# wireless.net
KiCad netlist of a schematic drawn in EAGLE
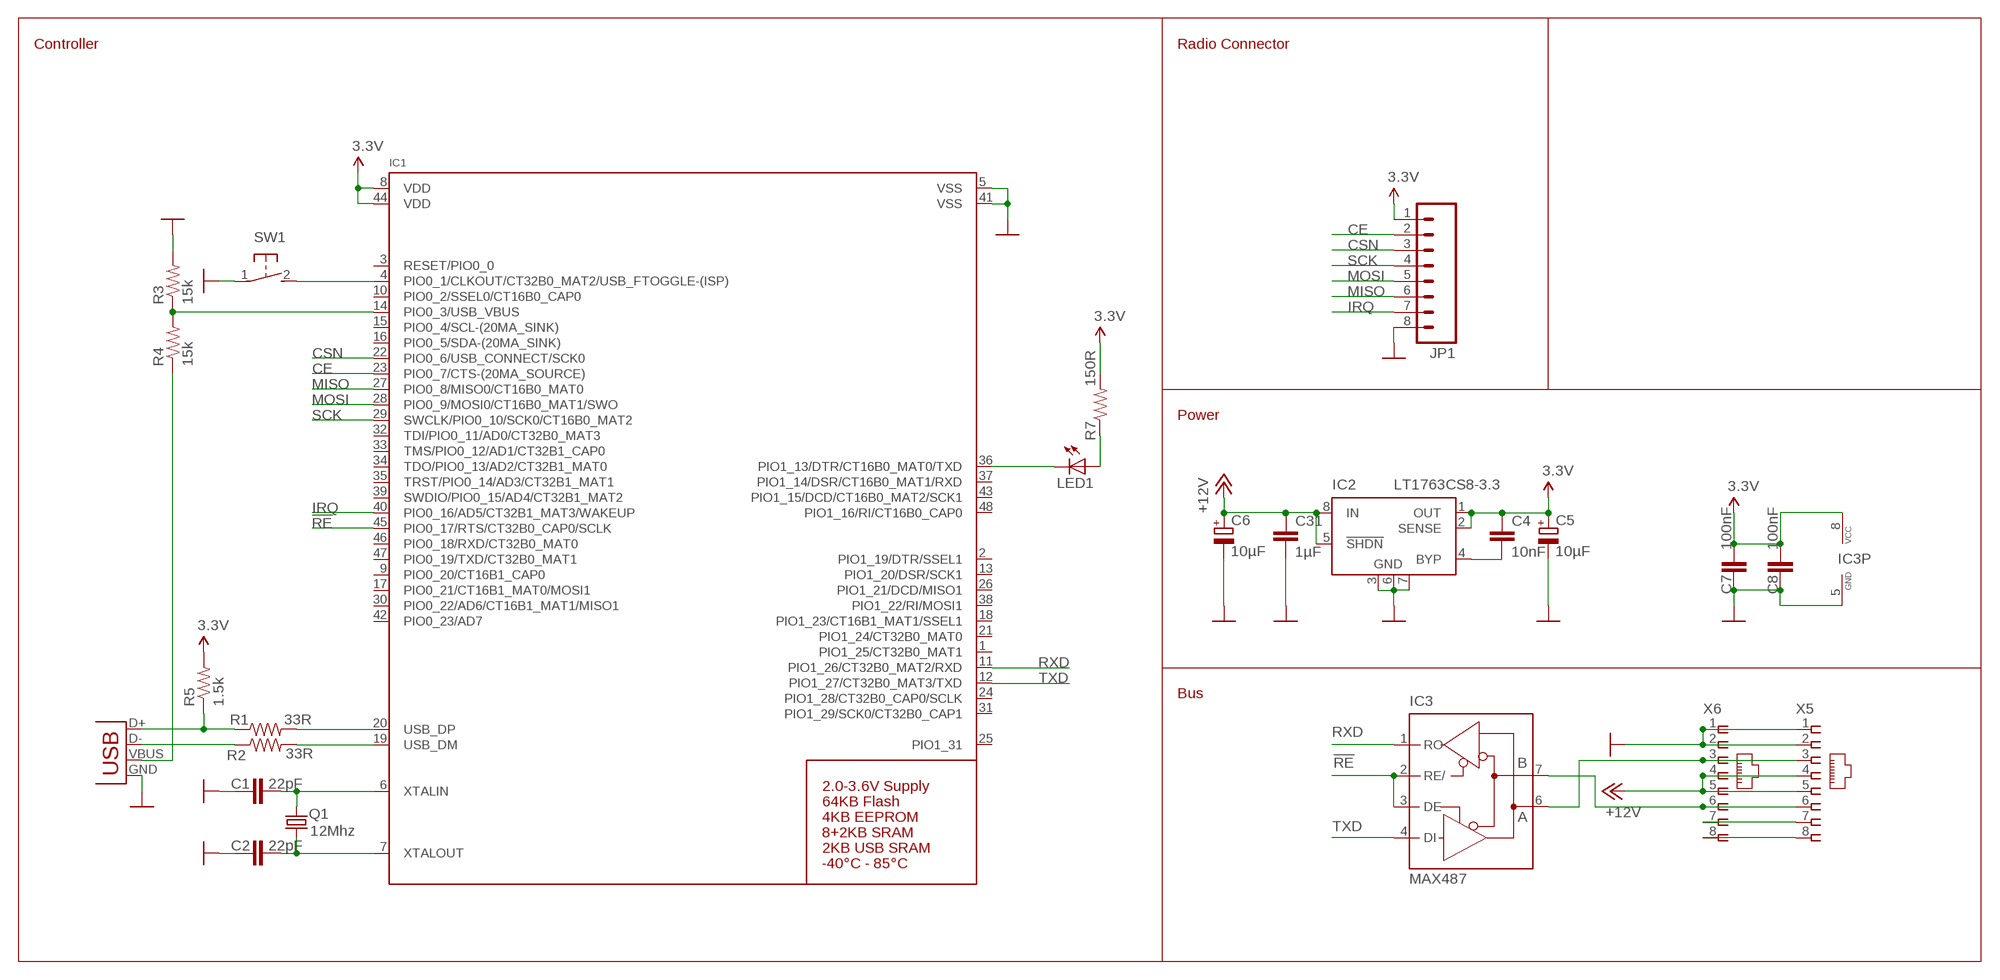
[diagram p0: schematic, sheet 1]

(export (version "E")
  (design (tool "Eeschema 10.0.6"))
  (components
    (comp (ref "C1")
      (value "22pF")
      (footprint "eagle-import:0402-CAP")
      (libsource (lib "eagle-import") (part "CAP0402-CAP"))
    )
    (comp (ref "C2")
      (value "22pF")
      (footprint "eagle-import:0402-CAP")
      (libsource (lib "eagle-import") (part "CAP0402-CAP"))
    )
    (comp (ref "C4")
      (value "10nF")
      (footprint "eagle-import:0402-CAP")
      (libsource (lib "eagle-import") (part "CAP0402-CAP"))
    )
    (comp (ref "C5")
      (value "10µF")
      (footprint "eagle-import:SMC_A")
      (libsource (lib "eagle-import") (part "CPOL-EUSMCA"))
    )
    (comp (ref "C6")
      (value "10µF")
      (footprint "eagle-import:SMC_D")
      (libsource (lib "eagle-import") (part "CPOL-EUSMCD"))
    )
    (comp (ref "C7")
      (value "100nF")
      (footprint "eagle-import:0402-CAP")
      (libsource (lib "eagle-import") (part "CAP0402-CAP"))
    )
    (comp (ref "C8")
      (value "100nF")
      (footprint "eagle-import:0402-CAP")
      (libsource (lib "eagle-import") (part "CAP0402-CAP"))
    )
    (comp (ref "C31")
      (value "1µF")
      (footprint "eagle-import:0805")
      (libsource (lib "eagle-import") (part "CAP0805"))
    )
    (comp (ref "IC1")
      (value "LPC1347_QFP48")
      (footprint "eagle-import:LQFP48")
      (libsource (lib "eagle-import") (part "LPC1347_QFP48"))
    )
    (comp (ref "IC2")
      (value "LT1763CS8-3.3")
      (footprint "eagle-import:SOIC8")
      (libsource (lib "eagle-import") (part "LT1763CS8-3.3"))
    )
    (comp (ref "IC3")
      (value "MAX487")
      (footprint "eagle-import:SO08")
      (fields (field (name "MF") "MAXIM") (field (name "MPN") "MAX481CSA"))
      (libsource (lib "eagle-import") (part "MAX481CSA"))
    )
    (comp (ref "JP1")
      (value "M081X08")
      (footprint "eagle-import:1X08")
      (libsource (lib "eagle-import") (part "M081X08"))
    )
    (comp (ref "LED1")
      (value "LEDCHIPLED_0805")
      (footprint "eagle-import:CHIPLED_0805")
      (libsource (lib "eagle-import") (part "LEDCHIPLED_0805"))
    )
    (comp (ref "Q1")
      (value "12Mhz")
      (footprint "eagle-import:X22")
      (libsource (lib "eagle-import") (part "X22-OSCILLATOR"))
    )
    (comp (ref "R1")
      (value "33R")
      (footprint "eagle-import:0402-RES")
      (libsource (lib "eagle-import") (part "RESISTOR0402-RES"))
    )
    (comp (ref "R2")
      (value "33R")
      (footprint "eagle-import:0402-RES")
      (libsource (lib "eagle-import") (part "RESISTOR0402-RES"))
    )
    (comp (ref "R3")
      (value "15k")
      (footprint "eagle-import:0402-RES")
      (libsource (lib "eagle-import") (part "RESISTOR0402-RES"))
    )
    (comp (ref "R4")
      (value "15k")
      (footprint "eagle-import:0402-RES")
      (libsource (lib "eagle-import") (part "RESISTOR0402-RES"))
    )
    (comp (ref "R5")
      (value "1.5k")
      (footprint "eagle-import:0402-RES")
      (libsource (lib "eagle-import") (part "RESISTOR0402-RES"))
    )
    (comp (ref "R7")
      (value "150R")
      (footprint "eagle-import:0402-RES")
      (libsource (lib "eagle-import") (part "RESISTOR0402-RES"))
    )
    (comp (ref "SW1")
      (value "SWITCH_MCTAEF")
      (footprint "eagle-import:SWITCH_MCTAEF")
      (libsource (lib "eagle-import") (part "SWITCH_MCTAEF"))
    )
    (comp (ref "X1")
      (value "USBSMD")
      (footprint "eagle-import:USB-MINIB")
      (libsource (lib "eagle-import") (part "USBSMD"))
    )
    (comp (ref "X5")
      (value "RJ45-8L-B")
      (footprint "eagle-import:RJ45-NO-SHIELD")
      (fields (field (name "MF") "TYCO ELECTRONICS"))
      (libsource (lib "eagle-import") (part "RJ45-8L-B"))
    )
    (comp (ref "X6")
      (value "RJ45-8L-B")
      (footprint "eagle-import:RJ45-NO-SHIELD")
      (fields (field (name "MF") "TYCO ELECTRONICS"))
      (libsource (lib "eagle-import") (part "RJ45-8L-B"))
    )
  )
  (nets
    (net (code "1") (name "+12V") (class "Default")
      (node (ref "C31") (pin "1") (pinfunction "1_1") (pintype "passive"))
      (node (ref "C6") (pin "+") (pinfunction "+_+") (pintype "passive"))
      (node (ref "IC2") (pin "5") (pinfunction "~{SHDN}_5") (pintype "input"))
      (node (ref "IC2") (pin "8") (pinfunction "IN_8") (pintype "input"))
      (node (ref "X5") (pin "4") (pinfunction "4_4") (pintype "passive"))
      (node (ref "X5") (pin "5") (pinfunction "5_5") (pintype "passive"))
      (node (ref "X6") (pin "4") (pinfunction "4_4") (pintype "passive"))
      (node (ref "X6") (pin "5") (pinfunction "5_5") (pintype "passive"))
    )
    (net (code "2") (name "/CE") (class "Default")
      (node (ref "IC1") (pin "23") (pinfunction "PIO0_7/CTS-(20MA_SOURCE)_23") (pintype "bidirectional"))
      (node (ref "JP1") (pin "2") (pinfunction "2_2") (pintype "passive"))
    )
    (net (code "3") (name "/CSN") (class "Default")
      (node (ref "IC1") (pin "22") (pinfunction "PIO0_6/USB_CONNECT/SCK0_22") (pintype "bidirectional"))
      (node (ref "JP1") (pin "3") (pinfunction "3_3") (pintype "passive"))
    )
    (net (code "4") (name "/IRQ") (class "Default")
      (node (ref "IC1") (pin "40") (pinfunction "PIO0_16/AD5/CT32B1_MAT3/WAKEUP_40") (pintype "bidirectional"))
      (node (ref "JP1") (pin "7") (pinfunction "7_7") (pintype "passive"))
    )
    (net (code "5") (name "/MISO") (class "Default")
      (node (ref "IC1") (pin "27") (pinfunction "PIO0_8/MISO0/CT16B0_MAT0_27") (pintype "bidirectional"))
      (node (ref "JP1") (pin "6") (pinfunction "6_6") (pintype "passive"))
    )
    (net (code "6") (name "/MOSI") (class "Default")
      (node (ref "IC1") (pin "28") (pinfunction "PIO0_9/MOSI0/CT16B0_MAT1/SWO_28") (pintype "bidirectional"))
      (node (ref "JP1") (pin "5") (pinfunction "5_5") (pintype "passive"))
    )
    (net (code "7") (name "/RXD") (class "Default")
      (node (ref "IC1") (pin "11") (pinfunction "PIO1_26/CT32B0_MAT2/RXD_11") (pintype "bidirectional"))
      (node (ref "IC3") (pin "1") (pinfunction "RO_1") (pintype "output"))
    )
    (net (code "8") (name "/SCK") (class "Default")
      (node (ref "IC1") (pin "29") (pinfunction "SWCLK/PIO0_10/SCK0/CT16B0_MAT2_29") (pintype "bidirectional"))
      (node (ref "JP1") (pin "4") (pinfunction "4_4") (pintype "passive"))
    )
    (net (code "9") (name "/TXD") (class "Default")
      (node (ref "IC1") (pin "12") (pinfunction "PIO1_27/CT32B0_MAT3/TXD_12") (pintype "bidirectional"))
      (node (ref "IC3") (pin "4") (pinfunction "DI_4") (pintype "input"))
    )
    (net (code "10") (name "/~{RE}") (class "Default")
      (node (ref "IC1") (pin "45") (pinfunction "PIO0_17/RTS/CT32B0_CAP0/SCLK_45") (pintype "bidirectional"))
      (node (ref "IC3") (pin "2") (pinfunction "RE/_2") (pintype "input"))
      (node (ref "IC3") (pin "3") (pinfunction "DE_3") (pintype "input"))
    )
    (net (code "11") (name "3.3V") (class "Default")
      (node (ref "C4") (pin "1") (pinfunction "1_1") (pintype "passive"))
      (node (ref "C5") (pin "+") (pinfunction "+_+") (pintype "passive"))
      (node (ref "C7") (pin "2") (pinfunction "2_2") (pintype "passive"))
      (node (ref "C8") (pin "2") (pinfunction "2_2") (pintype "passive"))
      (node (ref "IC1") (pin "44") (pinfunction "VDD_44") (pintype "power_in"))
      (node (ref "IC1") (pin "8") (pinfunction "VDD_8") (pintype "power_in"))
      (node (ref "IC2") (pin "1") (pinfunction "OUT_1") (pintype "passive"))
      (node (ref "IC2") (pin "2") (pinfunction "SENSE_2") (pintype "input"))
      (node (ref "IC3") (pin "8") (pinfunction "VCC_8") (pintype "power_in"))
      (node (ref "JP1") (pin "1") (pinfunction "1_1") (pintype "passive"))
      (node (ref "R5") (pin "2") (pinfunction "2_2") (pintype "passive"))
      (node (ref "R7") (pin "2") (pinfunction "2_2") (pintype "passive"))
    )
    (net (code "12") (name "GND") (class "Default")
      (node (ref "C1") (pin "1") (pinfunction "1_1") (pintype "passive"))
      (node (ref "C2") (pin "1") (pinfunction "1_1") (pintype "passive"))
      (node (ref "C31") (pin "2") (pinfunction "2_2") (pintype "passive"))
      (node (ref "C5") (pin "-") (pinfunction "-_-") (pintype "passive"))
      (node (ref "C6") (pin "-") (pinfunction "-_-") (pintype "passive"))
      (node (ref "C7") (pin "1") (pinfunction "1_1") (pintype "passive"))
      (node (ref "C8") (pin "1") (pinfunction "1_1") (pintype "passive"))
      (node (ref "IC1") (pin "41") (pinfunction "VSS_41") (pintype "power_in"))
      (node (ref "IC1") (pin "5") (pinfunction "VSS_5") (pintype "power_in"))
      (node (ref "IC2") (pin "3") (pinfunction "GND_3") (pintype "power_in"))
      (node (ref "IC2") (pin "6") (pinfunction "GND_6") (pintype "power_in"))
      (node (ref "IC2") (pin "7") (pinfunction "GND_7") (pintype "power_in"))
      (node (ref "IC3") (pin "5") (pinfunction "GND_5") (pintype "power_in"))
      (node (ref "JP1") (pin "8") (pinfunction "8_8") (pintype "passive"))
      (node (ref "R3") (pin "2") (pinfunction "2_2") (pintype "passive"))
      (node (ref "SW1") (pin "1") (pinfunction "1_1") (pintype "passive"))
      (node (ref "X1") (pin "GND") (pinfunction "GND_GND") (pintype "bidirectional"))
      (node (ref "X5") (pin "1") (pinfunction "1_1") (pintype "passive"))
      (node (ref "X5") (pin "2") (pinfunction "2_2") (pintype "passive"))
      (node (ref "X6") (pin "1") (pinfunction "1_1") (pintype "passive"))
      (node (ref "X6") (pin "2") (pinfunction "2_2") (pintype "passive"))
    )
    (net (code "13") (name "Net-(IC1-PIO0_1{slash}CLKOUT{slash}CT32B0_MAT2{slash}USB_FTOGGLE-(ISP))") (class "Default")
      (node (ref "IC1") (pin "4") (pinfunction "PIO0_1/CLKOUT/CT32B0_MAT2/USB_FTOGGLE-(ISP)_4") (pintype "bidirectional"))
      (node (ref "SW1") (pin "2") (pinfunction "2_2") (pintype "passive"))
    )
    (net (code "14") (name "Net-(IC1-PIO0_3{slash}USB_VBUS)") (class "Default")
      (node (ref "IC1") (pin "14") (pinfunction "PIO0_3/USB_VBUS_14") (pintype "bidirectional"))
      (node (ref "R3") (pin "1") (pinfunction "1_1") (pintype "passive"))
      (node (ref "R4") (pin "2") (pinfunction "2_2") (pintype "passive"))
    )
    (net (code "15") (name "Net-(IC1-PIO1_13{slash}DTR{slash}CT16B0_MAT0{slash}TXD)") (class "Default")
      (node (ref "IC1") (pin "36") (pinfunction "PIO1_13/DTR/CT16B0_MAT0/TXD_36") (pintype "bidirectional"))
      (node (ref "LED1") (pin "C") (pinfunction "C_C") (pintype "passive"))
    )
    (net (code "16") (name "Net-(IC1-USB_DM)") (class "Default")
      (node (ref "IC1") (pin "19") (pinfunction "USB_DM_19") (pintype "bidirectional"))
      (node (ref "R2") (pin "2") (pinfunction "2_2") (pintype "passive"))
    )
    (net (code "17") (name "Net-(IC1-USB_DP)") (class "Default")
      (node (ref "IC1") (pin "20") (pinfunction "USB_DP_20") (pintype "bidirectional"))
      (node (ref "R1") (pin "2") (pinfunction "2_2") (pintype "passive"))
    )
    (net (code "18") (name "Net-(IC1-XTALIN)") (class "Default")
      (node (ref "C1") (pin "2") (pinfunction "2_2") (pintype "passive"))
      (node (ref "IC1") (pin "6") (pinfunction "XTALIN_6") (pintype "bidirectional"))
      (node (ref "Q1") (pin "3") (pinfunction "2_3") (pintype "passive"))
    )
    (net (code "19") (name "Net-(IC1-XTALOUT)") (class "Default")
      (node (ref "C2") (pin "2") (pinfunction "2_2") (pintype "passive"))
      (node (ref "IC1") (pin "7") (pinfunction "XTALOUT_7") (pintype "bidirectional"))
      (node (ref "Q1") (pin "1") (pinfunction "1_1") (pintype "passive"))
    )
    (net (code "20") (name "Net-(IC2-BYP)") (class "Default")
      (node (ref "C4") (pin "2") (pinfunction "2_2") (pintype "passive"))
      (node (ref "IC2") (pin "4") (pinfunction "BYP_4") (pintype "input"))
    )
    (net (code "21") (name "Net-(IC3A-A)") (class "Default")
      (node (ref "IC3") (pin "6") (pinfunction "A_6") (pintype "passive"))
      (node (ref "X5") (pin "3") (pinfunction "3_3") (pintype "passive"))
      (node (ref "X6") (pin "3") (pinfunction "3_3") (pintype "passive"))
    )
    (net (code "22") (name "Net-(IC3A-B)") (class "Default")
      (node (ref "IC3") (pin "7") (pinfunction "B_7") (pintype "passive"))
      (node (ref "X5") (pin "6") (pinfunction "6_6") (pintype "passive"))
      (node (ref "X6") (pin "6") (pinfunction "6_6") (pintype "passive"))
    )
    (net (code "23") (name "Net-(LED1-PadA)") (class "Default")
      (node (ref "LED1") (pin "A") (pinfunction "A_A") (pintype "passive"))
      (node (ref "R7") (pin "1") (pinfunction "1_1") (pintype "passive"))
    )
    (net (code "24") (name "Net-(R1-Pad1)") (class "Default")
      (node (ref "R1") (pin "1") (pinfunction "1_1") (pintype "passive"))
      (node (ref "R5") (pin "1") (pinfunction "1_1") (pintype "passive"))
      (node (ref "X1") (pin "D+") (pinfunction "D+_D+") (pintype "bidirectional"))
    )
    (net (code "25") (name "Net-(R2-Pad1)") (class "Default")
      (node (ref "R2") (pin "1") (pinfunction "1_1") (pintype "passive"))
      (node (ref "X1") (pin "D-") (pinfunction "D-_D-") (pintype "bidirectional"))
    )
    (net (code "26") (name "Net-(R4-Pad1)") (class "Default")
      (node (ref "R4") (pin "1") (pinfunction "1_1") (pintype "passive"))
      (node (ref "X1") (pin "VBUS") (pinfunction "VBUS_VBUS") (pintype "bidirectional"))
    )
    (net (code "27") (name "Net-(X5-Pad7)") (class "Default")
      (node (ref "X5") (pin "7") (pinfunction "7_7") (pintype "passive"))
      (node (ref "X6") (pin "7") (pinfunction "7_7") (pintype "passive"))
    )
    (net (code "28") (name "Net-(X5-Pad8)") (class "Default")
      (node (ref "X5") (pin "8") (pinfunction "8_8") (pintype "passive"))
      (node (ref "X6") (pin "8") (pinfunction "8_8") (pintype "passive"))
    )
    (net (code "29") (name "unconnected-(IC1-PIO0_2{slash}SSEL0{slash}CT16B0_CAP0-Pad10)") (class "Default")
      (node (ref "IC1") (pin "10") (pinfunction "PIO0_2/SSEL0/CT16B0_CAP0_10") (pintype "bidirectional"))
    )
    (net (code "30") (name "unconnected-(IC1-PIO0_4{slash}SCL-(20MA_SINK)-Pad15)") (class "Default")
      (node (ref "IC1") (pin "15") (pinfunction "PIO0_4/SCL-(20MA_SINK)_15") (pintype "bidirectional"))
    )
    (net (code "31") (name "unconnected-(IC1-PIO0_5{slash}SDA-(20MA_SINK)-Pad16)") (class "Default")
      (node (ref "IC1") (pin "16") (pinfunction "PIO0_5/SDA-(20MA_SINK)_16") (pintype "bidirectional"))
    )
    (net (code "32") (name "unconnected-(IC1-PIO0_18{slash}RXD{slash}CT32B0_MAT0-Pad46)") (class "Default")
      (node (ref "IC1") (pin "46") (pinfunction "PIO0_18/RXD/CT32B0_MAT0_46") (pintype "bidirectional"))
    )
    (net (code "33") (name "unconnected-(IC1-PIO0_19{slash}TXD{slash}CT32B0_MAT1-Pad47)") (class "Default")
      (node (ref "IC1") (pin "47") (pinfunction "PIO0_19/TXD/CT32B0_MAT1_47") (pintype "bidirectional"))
    )
    (net (code "34") (name "unconnected-(IC1-PIO0_20{slash}CT16B1_CAP0-Pad9)") (class "Default")
      (node (ref "IC1") (pin "9") (pinfunction "PIO0_20/CT16B1_CAP0_9") (pintype "bidirectional"))
    )
    (net (code "35") (name "unconnected-(IC1-PIO0_21{slash}CT16B1_MAT0{slash}MOSI1-Pad17)") (class "Default")
      (node (ref "IC1") (pin "17") (pinfunction "PIO0_21/CT16B1_MAT0/MOSI1_17") (pintype "bidirectional"))
    )
    (net (code "36") (name "unconnected-(IC1-PIO0_22{slash}AD6{slash}CT16B1_MAT1{slash}MISO1-Pad30)") (class "Default")
      (node (ref "IC1") (pin "30") (pinfunction "PIO0_22/AD6/CT16B1_MAT1/MISO1_30") (pintype "bidirectional"))
    )
    (net (code "37") (name "unconnected-(IC1-PIO0_23{slash}AD7-Pad42)") (class "Default")
      (node (ref "IC1") (pin "42") (pinfunction "PIO0_23/AD7_42") (pintype "bidirectional"))
    )
    (net (code "38") (name "unconnected-(IC1-PIO1_14{slash}DSR{slash}CT16B0_MAT1{slash}RXD-Pad37)") (class "Default")
      (node (ref "IC1") (pin "37") (pinfunction "PIO1_14/DSR/CT16B0_MAT1/RXD_37") (pintype "bidirectional"))
    )
    (net (code "39") (name "unconnected-(IC1-PIO1_15{slash}DCD{slash}CT16B0_MAT2{slash}SCK1-Pad43)") (class "Default")
      (node (ref "IC1") (pin "43") (pinfunction "PIO1_15/DCD/CT16B0_MAT2/SCK1_43") (pintype "bidirectional"))
    )
    (net (code "40") (name "unconnected-(IC1-PIO1_16{slash}RI{slash}CT16B0_CAP0-Pad48)") (class "Default")
      (node (ref "IC1") (pin "48") (pinfunction "PIO1_16/RI/CT16B0_CAP0_48") (pintype "bidirectional"))
    )
    (net (code "41") (name "unconnected-(IC1-PIO1_19{slash}DTR{slash}SSEL1-Pad2)") (class "Default")
      (node (ref "IC1") (pin "2") (pinfunction "PIO1_19/DTR/SSEL1_2") (pintype "bidirectional"))
    )
    (net (code "42") (name "unconnected-(IC1-PIO1_20{slash}DSR{slash}SCK1-Pad13)") (class "Default")
      (node (ref "IC1") (pin "13") (pinfunction "PIO1_20/DSR/SCK1_13") (pintype "bidirectional"))
    )
    (net (code "43") (name "unconnected-(IC1-PIO1_21{slash}DCD{slash}MISO1-Pad26)") (class "Default")
      (node (ref "IC1") (pin "26") (pinfunction "PIO1_21/DCD/MISO1_26") (pintype "bidirectional"))
    )
    (net (code "44") (name "unconnected-(IC1-PIO1_22{slash}RI{slash}MOSI1-Pad38)") (class "Default")
      (node (ref "IC1") (pin "38") (pinfunction "PIO1_22/RI/MOSI1_38") (pintype "bidirectional"))
    )
    (net (code "45") (name "unconnected-(IC1-PIO1_23{slash}CT16B1_MAT1{slash}SSEL1-Pad18)") (class "Default")
      (node (ref "IC1") (pin "18") (pinfunction "PIO1_23/CT16B1_MAT1/SSEL1_18") (pintype "bidirectional"))
    )
    (net (code "46") (name "unconnected-(IC1-PIO1_24{slash}CT32B0_MAT0-Pad21)") (class "Default")
      (node (ref "IC1") (pin "21") (pinfunction "PIO1_24/CT32B0_MAT0_21") (pintype "bidirectional"))
    )
    (net (code "47") (name "unconnected-(IC1-PIO1_25{slash}CT32B0_MAT1-Pad1)") (class "Default")
      (node (ref "IC1") (pin "1") (pinfunction "PIO1_25/CT32B0_MAT1_1") (pintype "bidirectional"))
    )
    (net (code "48") (name "unconnected-(IC1-PIO1_28{slash}CT32B0_CAP0{slash}SCLK-Pad24)") (class "Default")
      (node (ref "IC1") (pin "24") (pinfunction "PIO1_28/CT32B0_CAP0/SCLK_24") (pintype "bidirectional"))
    )
    (net (code "49") (name "unconnected-(IC1-PIO1_29{slash}SCK0{slash}CT32B0_CAP1-Pad31)") (class "Default")
      (node (ref "IC1") (pin "31") (pinfunction "PIO1_29/SCK0/CT32B0_CAP1_31") (pintype "bidirectional"))
    )
    (net (code "50") (name "unconnected-(IC1-PIO1_31-Pad25)") (class "Default")
      (node (ref "IC1") (pin "25") (pinfunction "PIO1_31_25") (pintype "bidirectional"))
    )
    (net (code "51") (name "unconnected-(IC1-RESET{slash}PIO0_0-Pad3)") (class "Default")
      (node (ref "IC1") (pin "3") (pinfunction "RESET/PIO0_0_3") (pintype "bidirectional"))
    )
    (net (code "52") (name "unconnected-(IC1-SWDIO{slash}PIO0_15{slash}AD4{slash}CT32B1_MAT2-Pad39)") (class "Default")
      (node (ref "IC1") (pin "39") (pinfunction "SWDIO/PIO0_15/AD4/CT32B1_MAT2_39") (pintype "bidirectional"))
    )
    (net (code "53") (name "unconnected-(IC1-TDI{slash}PIO0_11{slash}AD0{slash}CT32B0_MAT3-Pad32)") (class "Default")
      (node (ref "IC1") (pin "32") (pinfunction "TDI/PIO0_11/AD0/CT32B0_MAT3_32") (pintype "bidirectional"))
    )
    (net (code "54") (name "unconnected-(IC1-TDO{slash}PIO0_13{slash}AD2{slash}CT32B1_MAT0-Pad34)") (class "Default")
      (node (ref "IC1") (pin "34") (pinfunction "TDO/PIO0_13/AD2/CT32B1_MAT0_34") (pintype "bidirectional"))
    )
    (net (code "55") (name "unconnected-(IC1-TMS{slash}PIO0_12{slash}AD1{slash}CT32B1_CAP0-Pad33)") (class "Default")
      (node (ref "IC1") (pin "33") (pinfunction "TMS/PIO0_12/AD1/CT32B1_CAP0_33") (pintype "bidirectional"))
    )
    (net (code "56") (name "unconnected-(IC1-TRST{slash}PIO0_14{slash}AD3{slash}CT32B1_MAT1-Pad35)") (class "Default")
      (node (ref "IC1") (pin "35") (pinfunction "TRST/PIO0_14/AD3/CT32B1_MAT1_35") (pintype "bidirectional"))
    )
  )
)
